# Electronicsmb.net
KiCad netlist of a schematic drawn in EAGLE
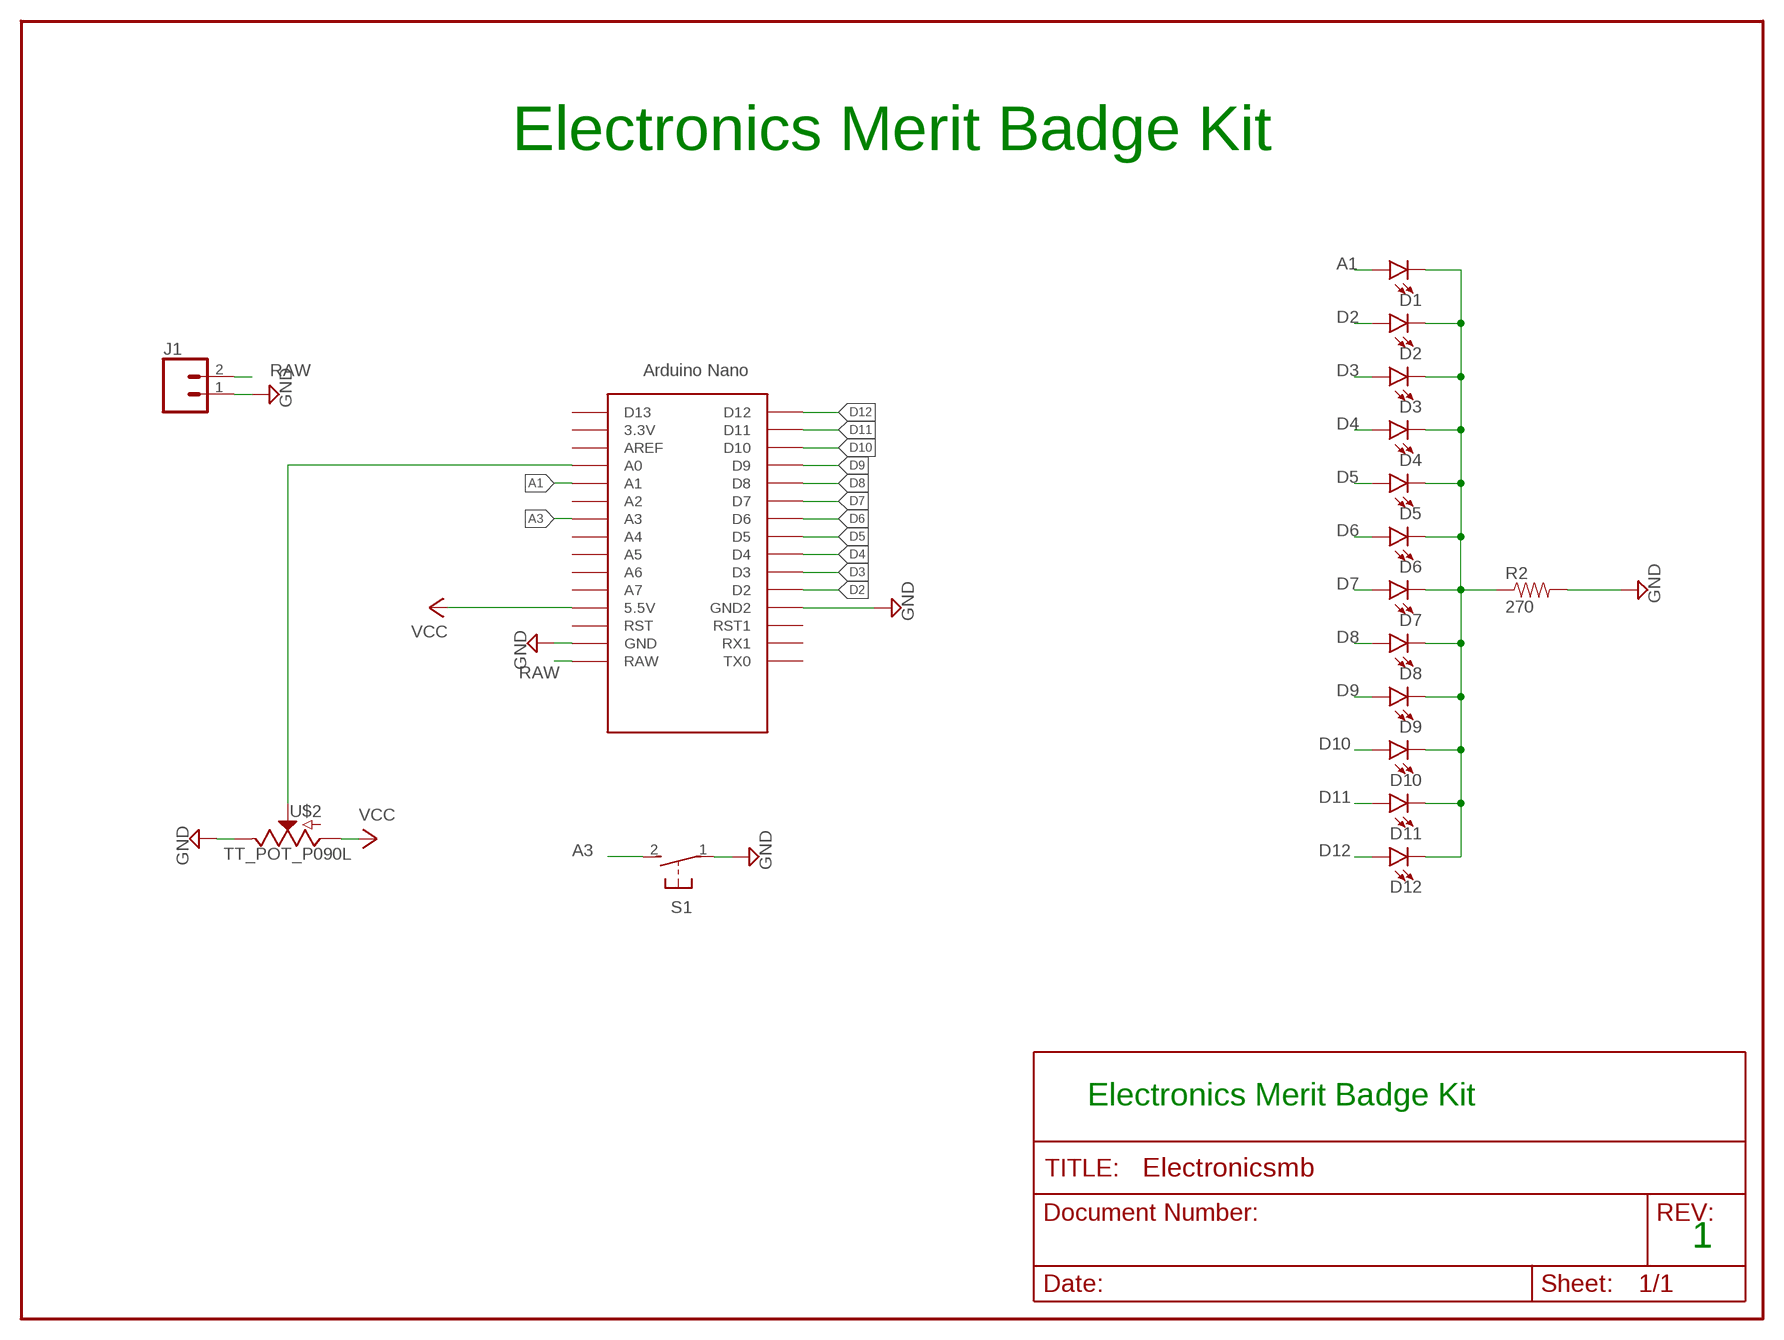
[diagram p0: schematic, sheet 1]

(export (version "E")
  (design (tool "Eeschema 10.0.6"))
  (components
    (comp (ref "D1")
      (value "LED5MM")
      (footprint "eagle-import:LED_5MM")
      (libsource (lib "eagle-import") (part "LED5MM"))
    )
    (comp (ref "D2")
      (value "LED5MM")
      (footprint "eagle-import:LED_5MM")
      (libsource (lib "eagle-import") (part "LED5MM"))
    )
    (comp (ref "D3")
      (value "LED5MM")
      (footprint "eagle-import:LED_5MM")
      (libsource (lib "eagle-import") (part "LED5MM"))
    )
    (comp (ref "D4")
      (value "LED5MM")
      (footprint "eagle-import:LED_5MM")
      (libsource (lib "eagle-import") (part "LED5MM"))
    )
    (comp (ref "D5")
      (value "LED5MM")
      (footprint "eagle-import:LED_5MM")
      (libsource (lib "eagle-import") (part "LED5MM"))
    )
    (comp (ref "D6")
      (value "LED5MM")
      (footprint "eagle-import:LED_5MM")
      (libsource (lib "eagle-import") (part "LED5MM"))
    )
    (comp (ref "D7")
      (value "LED5MM")
      (footprint "eagle-import:LED_5MM")
      (libsource (lib "eagle-import") (part "LED5MM"))
    )
    (comp (ref "D8")
      (value "LED5MM")
      (footprint "eagle-import:LED_5MM")
      (libsource (lib "eagle-import") (part "LED5MM"))
    )
    (comp (ref "D9")
      (value "LED5MM")
      (footprint "eagle-import:LED_5MM")
      (libsource (lib "eagle-import") (part "LED5MM"))
    )
    (comp (ref "D10")
      (value "LED5MM")
      (footprint "eagle-import:LED_5MM")
      (libsource (lib "eagle-import") (part "LED5MM"))
    )
    (comp (ref "D11")
      (value "LED5MM")
      (footprint "eagle-import:LED_5MM")
      (libsource (lib "eagle-import") (part "LED5MM"))
    )
    (comp (ref "D12")
      (value "LED5MM")
      (footprint "eagle-import:LED_5MM")
      (libsource (lib "eagle-import") (part "LED5MM"))
    )
    (comp (ref "J1")
      (value "CONN_02")
      (footprint "eagle-import:1X02")
      (libsource (lib "eagle-import") (part "CONN_02"))
    )
    (comp (ref "R2")
      (value "270")
      (footprint "eagle-import:AXIAL-0.4")
      (libsource (lib "eagle-import") (part "RESISTORPTH-1/4W"))
    )
    (comp (ref "S1")
      (value "31-XX")
      (footprint "eagle-import:B3F-31XX")
      (fields (field (name "MPN") "B3F-3100"))
      (libsource (lib "eagle-import") (part "31-XX"))
    )
    (comp (ref "U$1")
      (value "NANO")
      (footprint "eagle-import:NANO")
      (libsource (lib "eagle-import") (part "NANO"))
    )
    (comp (ref "U$2")
      (value "TT_POT_P090L")
      (footprint "eagle-import:TT_POT")
      (libsource (lib "eagle-import") (part "TT_POT_P090L"))
    )
  )
  (nets
    (net (code "1") (name "/RAW") (class "Default")
      (node (ref "J1") (pin "2") (pinfunction "2_2") (pintype "passive"))
      (node (ref "U$1") (pin "RAW") (pinfunction "RAW_RAW") (pintype "bidirectional"))
    )
    (net (code "2") (name "A1") (class "Default")
      (node (ref "D1") (pin "A") (pinfunction "A_A") (pintype "passive"))
      (node (ref "U$1") (pin "A1") (pinfunction "A1_A1") (pintype "bidirectional"))
    )
    (net (code "3") (name "A3") (class "Default")
      (node (ref "S1") (pin "2") (pinfunction "S_2") (pintype "passive"))
      (node (ref "U$1") (pin "A3") (pinfunction "A3_A3") (pintype "bidirectional"))
    )
    (net (code "4") (name "D2") (class "Default")
      (node (ref "D2") (pin "A") (pinfunction "A_A") (pintype "passive"))
      (node (ref "U$1") (pin "D2") (pinfunction "D2_D2") (pintype "bidirectional"))
    )
    (net (code "5") (name "D3") (class "Default")
      (node (ref "D3") (pin "A") (pinfunction "A_A") (pintype "passive"))
      (node (ref "U$1") (pin "D3") (pinfunction "D3_D3") (pintype "bidirectional"))
    )
    (net (code "6") (name "D4") (class "Default")
      (node (ref "D4") (pin "A") (pinfunction "A_A") (pintype "passive"))
      (node (ref "U$1") (pin "D4") (pinfunction "D4_D4") (pintype "bidirectional"))
    )
    (net (code "7") (name "D5") (class "Default")
      (node (ref "D5") (pin "A") (pinfunction "A_A") (pintype "passive"))
      (node (ref "U$1") (pin "D5") (pinfunction "D5_D5") (pintype "bidirectional"))
    )
    (net (code "8") (name "D6") (class "Default")
      (node (ref "D6") (pin "A") (pinfunction "A_A") (pintype "passive"))
      (node (ref "U$1") (pin "D6") (pinfunction "D6_D6") (pintype "bidirectional"))
    )
    (net (code "9") (name "D7") (class "Default")
      (node (ref "D7") (pin "A") (pinfunction "A_A") (pintype "passive"))
      (node (ref "U$1") (pin "D7") (pinfunction "D7_D7") (pintype "bidirectional"))
    )
    (net (code "10") (name "D8") (class "Default")
      (node (ref "D8") (pin "A") (pinfunction "A_A") (pintype "passive"))
      (node (ref "U$1") (pin "D8") (pinfunction "D8_D8") (pintype "bidirectional"))
    )
    (net (code "11") (name "D9") (class "Default")
      (node (ref "D9") (pin "A") (pinfunction "A_A") (pintype "passive"))
      (node (ref "U$1") (pin "D9") (pinfunction "D9_D9") (pintype "bidirectional"))
    )
    (net (code "12") (name "D10") (class "Default")
      (node (ref "D10") (pin "A") (pinfunction "A_A") (pintype "passive"))
      (node (ref "U$1") (pin "D10") (pinfunction "D10_D10") (pintype "bidirectional"))
    )
    (net (code "13") (name "D11") (class "Default")
      (node (ref "D11") (pin "A") (pinfunction "A_A") (pintype "passive"))
      (node (ref "U$1") (pin "D11") (pinfunction "D11_D11") (pintype "bidirectional"))
    )
    (net (code "14") (name "D12") (class "Default")
      (node (ref "D12") (pin "A") (pinfunction "A_A") (pintype "passive"))
      (node (ref "U$1") (pin "D12") (pinfunction "D12_D12") (pintype "bidirectional"))
    )
    (net (code "15") (name "GND") (class "Default")
      (node (ref "J1") (pin "1") (pinfunction "1_1") (pintype "passive"))
      (node (ref "R2") (pin "P$2") (pinfunction "2_P$2") (pintype "passive"))
      (node (ref "S1") (pin "1") (pinfunction "P_1") (pintype "passive"))
      (node (ref "U$1") (pin "GND") (pinfunction "GND_GND") (pintype "bidirectional"))
      (node (ref "U$1") (pin "GND1") (pinfunction "GND2_GND1") (pintype "bidirectional"))
      (node (ref "U$2") (pin "P$3") (pinfunction "E_P$3") (pintype "passive"))
    )
    (net (code "16") (name "Net-(D1-C)") (class "Default")
      (node (ref "D1") (pin "K") (pinfunction "C_K") (pintype "passive"))
      (node (ref "D10") (pin "K") (pinfunction "C_K") (pintype "passive"))
      (node (ref "D11") (pin "K") (pinfunction "C_K") (pintype "passive"))
      (node (ref "D12") (pin "K") (pinfunction "C_K") (pintype "passive"))
      (node (ref "D2") (pin "K") (pinfunction "C_K") (pintype "passive"))
      (node (ref "D3") (pin "K") (pinfunction "C_K") (pintype "passive"))
      (node (ref "D4") (pin "K") (pinfunction "C_K") (pintype "passive"))
      (node (ref "D5") (pin "K") (pinfunction "C_K") (pintype "passive"))
      (node (ref "D6") (pin "K") (pinfunction "C_K") (pintype "passive"))
      (node (ref "D7") (pin "K") (pinfunction "C_K") (pintype "passive"))
      (node (ref "D8") (pin "K") (pinfunction "C_K") (pintype "passive"))
      (node (ref "D9") (pin "K") (pinfunction "C_K") (pintype "passive"))
      (node (ref "R2") (pin "P$1") (pinfunction "1_P$1") (pintype "passive"))
    )
    (net (code "17") (name "Net-(U$2-S)") (class "Default")
      (node (ref "U$1") (pin "A0") (pinfunction "A0_A0") (pintype "bidirectional"))
      (node (ref "U$2") (pin "P$2") (pinfunction "S_P$2") (pintype "passive"))
    )
    (net (code "18") (name "VCC") (class "Default")
      (node (ref "U$1") (pin "5V") (pinfunction "5.5V_5V") (pintype "bidirectional"))
      (node (ref "U$2") (pin "P$1") (pinfunction "A_P$1") (pintype "passive"))
    )
    (net (code "19") (name "unconnected-(U$1-Pad3.3V)") (class "Default")
      (node (ref "U$1") (pin "3.3V") (pinfunction "3.3V_3.3V") (pintype "bidirectional"))
    )
    (net (code "20") (name "unconnected-(U$1-PadA2)") (class "Default")
      (node (ref "U$1") (pin "A2") (pinfunction "A2_A2") (pintype "bidirectional"))
    )
    (net (code "21") (name "unconnected-(U$1-PadA4)") (class "Default")
      (node (ref "U$1") (pin "A4") (pinfunction "A4_A4") (pintype "bidirectional"))
    )
    (net (code "22") (name "unconnected-(U$1-PadA5)") (class "Default")
      (node (ref "U$1") (pin "A5") (pinfunction "A5_A5") (pintype "bidirectional"))
    )
    (net (code "23") (name "unconnected-(U$1-PadA6)") (class "Default")
      (node (ref "U$1") (pin "A6") (pinfunction "A6_A6") (pintype "bidirectional"))
    )
    (net (code "24") (name "unconnected-(U$1-PadA7)") (class "Default")
      (node (ref "U$1") (pin "A7") (pinfunction "A7_A7") (pintype "bidirectional"))
    )
    (net (code "25") (name "unconnected-(U$1-PadAREF)") (class "Default")
      (node (ref "U$1") (pin "AREF") (pinfunction "AREF_AREF") (pintype "bidirectional"))
    )
    (net (code "26") (name "unconnected-(U$1-PadD13)") (class "Default")
      (node (ref "U$1") (pin "D13") (pinfunction "D13_D13") (pintype "bidirectional"))
    )
    (net (code "27") (name "unconnected-(U$1-PadICSP1)") (class "Default")
      (node (ref "U$1") (pin "ICSP1") (pinfunction "ICSP1_ICSP1") (pintype "bidirectional"))
    )
    (net (code "28") (name "unconnected-(U$1-PadICSP2)") (class "Default")
      (node (ref "U$1") (pin "ICSP2") (pinfunction "ICSP2_ICSP2") (pintype "bidirectional"))
    )
    (net (code "29") (name "unconnected-(U$1-PadICSP3)") (class "Default")
      (node (ref "U$1") (pin "ICSP3") (pinfunction "ICSP3_ICSP3") (pintype "bidirectional"))
    )
    (net (code "30") (name "unconnected-(U$1-PadICSP4)") (class "Default")
      (node (ref "U$1") (pin "ICSP4") (pinfunction "ICSP4_ICSP4") (pintype "bidirectional"))
    )
    (net (code "31") (name "unconnected-(U$1-PadICSP5)") (class "Default")
      (node (ref "U$1") (pin "ICSP5") (pinfunction "ICSP5_ICSP5") (pintype "bidirectional"))
    )
    (net (code "32") (name "unconnected-(U$1-PadICSP6)") (class "Default")
      (node (ref "U$1") (pin "ICSP6") (pinfunction "ICSP6_ICSP6") (pintype "bidirectional"))
    )
    (net (code "33") (name "unconnected-(U$1-PadRST)") (class "Default")
      (node (ref "U$1") (pin "RST") (pinfunction "RST_RST") (pintype "bidirectional"))
    )
    (net (code "34") (name "unconnected-(U$1-PadRST1)") (class "Default")
      (node (ref "U$1") (pin "RST1") (pinfunction "RST1_RST1") (pintype "bidirectional"))
    )
    (net (code "35") (name "unconnected-(U$1-PadRX1)") (class "Default")
      (node (ref "U$1") (pin "RX1") (pinfunction "RX1_RX1") (pintype "bidirectional"))
    )
    (net (code "36") (name "unconnected-(U$1-PadTX0)") (class "Default")
      (node (ref "U$1") (pin "TX0") (pinfunction "TX0_TX0") (pintype "bidirectional"))
    )
  )
)
